# dsPIC_filter.net
KiCad netlist of a schematic drawn in Altium Designer
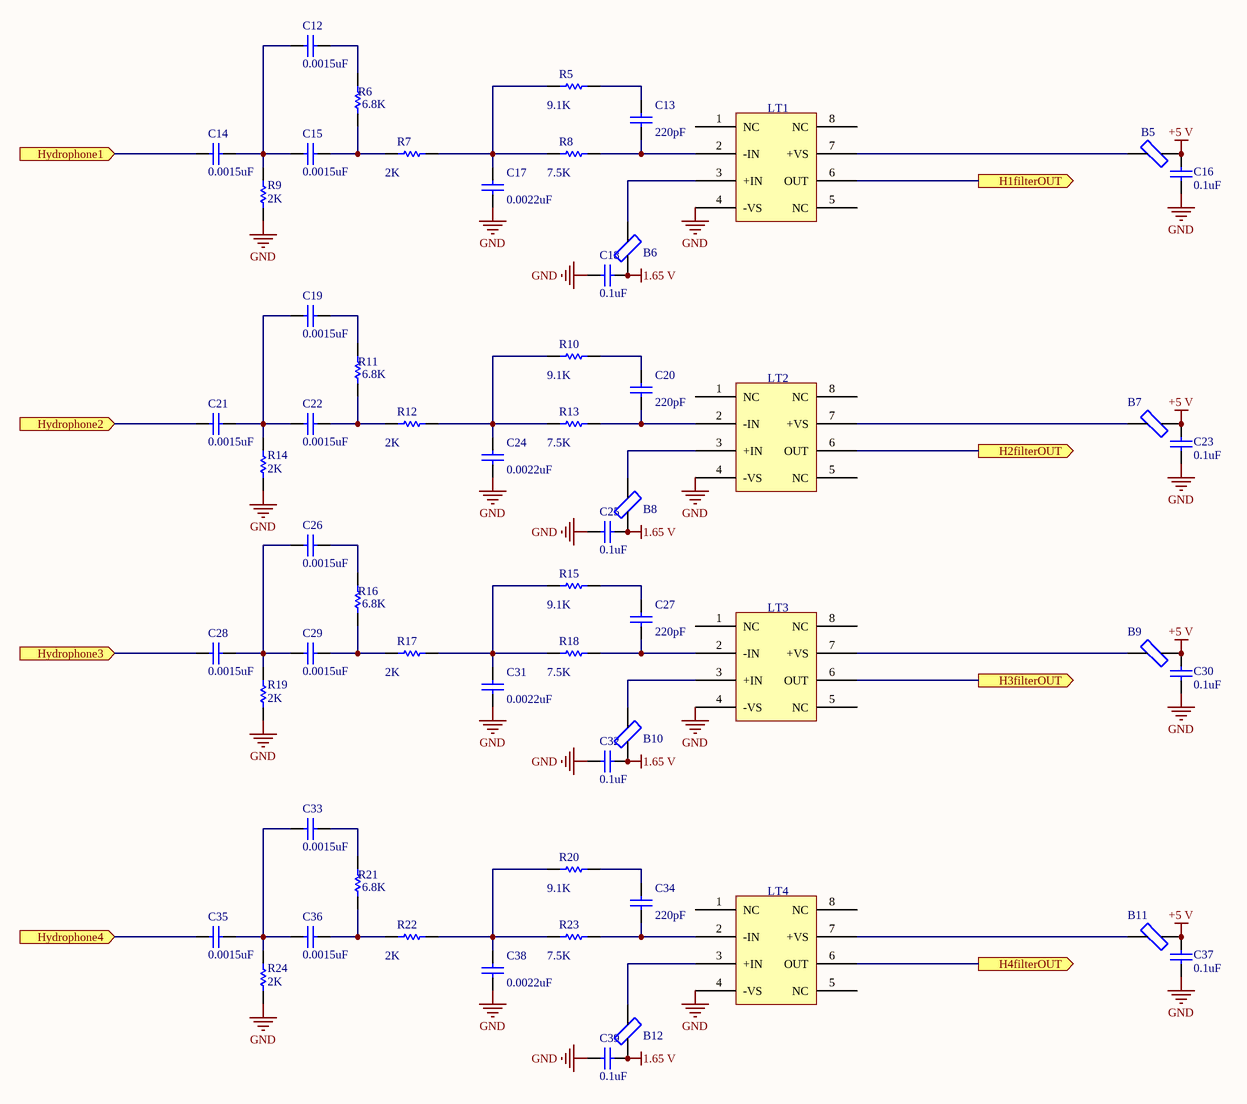
[diagram p0: dsPIC_filter.SchDoc]

(export (version "E")
  (design (tool "Eeschema 10.0.6"))
  (components
    (comp (ref "B5")
      (value "Ferrite Bead")
      (footprint "Capacitor 0603")
      (libsource (lib "PMUD") (part "Ferrite Bead"))
    )
    (comp (ref "B6")
      (value "Ferrite Bead")
      (footprint "Capacitor 0603")
      (libsource (lib "PMUD") (part "Ferrite Bead"))
    )
    (comp (ref "B7")
      (value "Ferrite Bead")
      (footprint "Capacitor 0603")
      (libsource (lib "PMUD") (part "Ferrite Bead"))
    )
    (comp (ref "B8")
      (value "Ferrite Bead")
      (footprint "Capacitor 0603")
      (libsource (lib "PMUD") (part "Ferrite Bead"))
    )
    (comp (ref "B9")
      (value "Ferrite Bead")
      (footprint "Capacitor 0603")
      (libsource (lib "PMUD") (part "Ferrite Bead"))
    )
    (comp (ref "B10")
      (value "Ferrite Bead")
      (footprint "Capacitor 0603")
      (libsource (lib "PMUD") (part "Ferrite Bead"))
    )
    (comp (ref "B11")
      (value "Ferrite Bead")
      (footprint "Capacitor 0603")
      (libsource (lib "PMUD") (part "Ferrite Bead"))
    )
    (comp (ref "B12")
      (value "Ferrite Bead")
      (footprint "Capacitor 0603")
      (libsource (lib "PMUD") (part "Ferrite Bead"))
    )
    (comp (ref "C12")
      (value "0.0015uF")
      (footprint "Capacitor 0603")
      (description "Capacitor")
      (fields (field (name "PUBLISHER") "Altium Limited"))
      (libsource (lib "My Parts Sch Components") (part "Cap"))
    )
    (comp (ref "C13")
      (value "220pF")
      (footprint "Capacitor 0603")
      (description "Capacitor")
      (fields (field (name "PUBLISHER") "Altium Limited"))
      (libsource (lib "My Parts Sch Components") (part "Cap"))
    )
    (comp (ref "C14")
      (value "0.0015uF")
      (footprint "Capacitor 0603")
      (description "Capacitor")
      (fields (field (name "PUBLISHER") "Altium Limited"))
      (libsource (lib "My Parts Sch Components") (part "Cap"))
    )
    (comp (ref "C15")
      (value "0.0015uF")
      (footprint "Capacitor 0603")
      (description "Capacitor")
      (fields (field (name "PUBLISHER") "Altium Limited"))
      (libsource (lib "My Parts Sch Components") (part "Cap"))
    )
    (comp (ref "C16")
      (value "0.1uF")
      (footprint "C1206")
      (description "Capacitor (Semiconductor SIM Model)")
      (fields (field (name "Comment") ".1uF 20V Ceramic Low ESR") (field (name "PUBLISHER") "Altium Limited"))
      (libsource (lib "Miscellaneous Devices") (part "Cap Semi"))
    )
    (comp (ref "C17")
      (value "0.0022uF")
      (footprint "Capacitor 0603")
      (description "Capacitor")
      (fields (field (name "PUBLISHER") "Altium Limited"))
      (libsource (lib "My Parts Sch Components") (part "Cap"))
    )
    (comp (ref "C18")
      (value "0.1uF")
      (footprint "C1206")
      (description "Capacitor (Semiconductor SIM Model)")
      (fields (field (name "Comment") ".1uF 20V Ceramic Low ESR") (field (name "PUBLISHER") "Altium Limited"))
      (libsource (lib "Miscellaneous Devices") (part "Cap Semi"))
    )
    (comp (ref "C19")
      (value "0.0015uF")
      (footprint "Capacitor 0603")
      (description "Capacitor")
      (fields (field (name "PUBLISHER") "Altium Limited"))
      (libsource (lib "My Parts Sch Components") (part "Cap"))
    )
    (comp (ref "C20")
      (value "220pF")
      (footprint "Capacitor 0603")
      (description "Capacitor")
      (fields (field (name "PUBLISHER") "Altium Limited"))
      (libsource (lib "My Parts Sch Components") (part "Cap"))
    )
    (comp (ref "C21")
      (value "0.0015uF")
      (footprint "Capacitor 0603")
      (description "Capacitor")
      (fields (field (name "PUBLISHER") "Altium Limited"))
      (libsource (lib "My Parts Sch Components") (part "Cap"))
    )
    (comp (ref "C22")
      (value "0.0015uF")
      (footprint "Capacitor 0603")
      (description "Capacitor")
      (fields (field (name "PUBLISHER") "Altium Limited"))
      (libsource (lib "My Parts Sch Components") (part "Cap"))
    )
    (comp (ref "C23")
      (value "0.1uF")
      (footprint "C1206")
      (description "Capacitor (Semiconductor SIM Model)")
      (fields (field (name "Comment") ".1uF 20V Ceramic Low ESR") (field (name "PUBLISHER") "Altium Limited"))
      (libsource (lib "Miscellaneous Devices") (part "Cap Semi"))
    )
    (comp (ref "C24")
      (value "0.0022uF")
      (footprint "Capacitor 0603")
      (description "Capacitor")
      (fields (field (name "PUBLISHER") "Altium Limited"))
      (libsource (lib "My Parts Sch Components") (part "Cap"))
    )
    (comp (ref "C25")
      (value "0.1uF")
      (footprint "C1206")
      (description "Capacitor (Semiconductor SIM Model)")
      (fields (field (name "Comment") ".1uF 20V Ceramic Low ESR") (field (name "PUBLISHER") "Altium Limited"))
      (libsource (lib "Miscellaneous Devices") (part "Cap Semi"))
    )
    (comp (ref "C26")
      (value "0.0015uF")
      (footprint "Capacitor 0603")
      (description "Capacitor")
      (fields (field (name "PUBLISHER") "Altium Limited"))
      (libsource (lib "My Parts Sch Components") (part "Cap"))
    )
    (comp (ref "C27")
      (value "220pF")
      (footprint "Capacitor 0603")
      (description "Capacitor")
      (fields (field (name "PUBLISHER") "Altium Limited"))
      (libsource (lib "My Parts Sch Components") (part "Cap"))
    )
    (comp (ref "C28")
      (value "0.0015uF")
      (footprint "Capacitor 0603")
      (description "Capacitor")
      (fields (field (name "PUBLISHER") "Altium Limited"))
      (libsource (lib "My Parts Sch Components") (part "Cap"))
    )
    (comp (ref "C29")
      (value "0.0015uF")
      (footprint "Capacitor 0603")
      (description "Capacitor")
      (fields (field (name "PUBLISHER") "Altium Limited"))
      (libsource (lib "My Parts Sch Components") (part "Cap"))
    )
    (comp (ref "C30")
      (value "0.1uF")
      (footprint "C1206")
      (description "Capacitor (Semiconductor SIM Model)")
      (fields (field (name "Comment") ".1uF 20V Ceramic Low ESR") (field (name "PUBLISHER") "Altium Limited"))
      (libsource (lib "Miscellaneous Devices") (part "Cap Semi"))
    )
    (comp (ref "C31")
      (value "0.0022uF")
      (footprint "Capacitor 0603")
      (description "Capacitor")
      (fields (field (name "PUBLISHER") "Altium Limited"))
      (libsource (lib "My Parts Sch Components") (part "Cap"))
    )
    (comp (ref "C32")
      (value "0.1uF")
      (footprint "C1206")
      (description "Capacitor (Semiconductor SIM Model)")
      (fields (field (name "Comment") ".1uF 20V Ceramic Low ESR") (field (name "PUBLISHER") "Altium Limited"))
      (libsource (lib "Miscellaneous Devices") (part "Cap Semi"))
    )
    (comp (ref "C33")
      (value "0.0015uF")
      (footprint "Capacitor 0603")
      (description "Capacitor")
      (fields (field (name "PUBLISHER") "Altium Limited"))
      (libsource (lib "My Parts Sch Components") (part "Cap"))
    )
    (comp (ref "C34")
      (value "220pF")
      (footprint "Capacitor 0603")
      (description "Capacitor")
      (fields (field (name "PUBLISHER") "Altium Limited"))
      (libsource (lib "My Parts Sch Components") (part "Cap"))
    )
    (comp (ref "C35")
      (value "0.0015uF")
      (footprint "Capacitor 0603")
      (description "Capacitor")
      (fields (field (name "PUBLISHER") "Altium Limited"))
      (libsource (lib "My Parts Sch Components") (part "Cap"))
    )
    (comp (ref "C36")
      (value "0.0015uF")
      (footprint "Capacitor 0603")
      (description "Capacitor")
      (fields (field (name "PUBLISHER") "Altium Limited"))
      (libsource (lib "My Parts Sch Components") (part "Cap"))
    )
    (comp (ref "C37")
      (value "0.1uF")
      (footprint "C1206")
      (description "Capacitor (Semiconductor SIM Model)")
      (fields (field (name "Comment") ".1uF 20V Ceramic Low ESR") (field (name "PUBLISHER") "Altium Limited"))
      (libsource (lib "Miscellaneous Devices") (part "Cap Semi"))
    )
    (comp (ref "C38")
      (value "0.0022uF")
      (footprint "Capacitor 0603")
      (description "Capacitor")
      (fields (field (name "PUBLISHER") "Altium Limited"))
      (libsource (lib "My Parts Sch Components") (part "Cap"))
    )
    (comp (ref "C39")
      (value "0.1uF")
      (footprint "C1206")
      (description "Capacitor (Semiconductor SIM Model)")
      (fields (field (name "Comment") ".1uF 20V Ceramic Low ESR") (field (name "PUBLISHER") "Altium Limited"))
      (libsource (lib "Miscellaneous Devices") (part "Cap Semi"))
    )
    (comp (ref "LT1")
      (value "LT1677 SO8 Package")
      (footprint "SO8")
      (libsource (lib "My Parts Sch Components") (part "LT1677"))
    )
    (comp (ref "LT2")
      (value "LT1677 SO8 Package")
      (footprint "SO8")
      (libsource (lib "My Parts Sch Components") (part "LT1677"))
    )
    (comp (ref "LT3")
      (value "LT1677 SO8 Package")
      (footprint "SO8")
      (libsource (lib "My Parts Sch Components") (part "LT1677"))
    )
    (comp (ref "LT4")
      (value "LT1677 SO8 Package")
      (footprint "SO8")
      (libsource (lib "My Parts Sch Components") (part "LT1677"))
    )
    (comp (ref "R5")
      (value "9.1K")
      (footprint "Capacitor 0603")
      (description "Resistor")
      (fields (field (name "PUBLISHER") "Altium Limited"))
      (libsource (lib "My Parts Sch Components") (part "Res1"))
    )
    (comp (ref "R6")
      (value "6.8K")
      (footprint "Capacitor 0603")
      (description "Resistor")
      (fields (field (name "PUBLISHER") "Altium Limited"))
      (libsource (lib "My Parts Sch Components") (part "Res1"))
    )
    (comp (ref "R7")
      (value "2K")
      (footprint "Capacitor 0603")
      (description "Resistor")
      (fields (field (name "PUBLISHER") "Altium Limited"))
      (libsource (lib "My Parts Sch Components") (part "Res1"))
    )
    (comp (ref "R8")
      (value "7.5K")
      (footprint "Capacitor 0603")
      (description "Resistor")
      (fields (field (name "PUBLISHER") "Altium Limited"))
      (libsource (lib "My Parts Sch Components") (part "Res1"))
    )
    (comp (ref "R9")
      (value "2K")
      (footprint "Capacitor 0603")
      (description "Resistor")
      (fields (field (name "PUBLISHER") "Altium Limited"))
      (libsource (lib "My Parts Sch Components") (part "Res1"))
    )
    (comp (ref "R10")
      (value "9.1K")
      (footprint "Capacitor 0603")
      (description "Resistor")
      (fields (field (name "PUBLISHER") "Altium Limited"))
      (libsource (lib "My Parts Sch Components") (part "Res1"))
    )
    (comp (ref "R11")
      (value "6.8K")
      (footprint "Capacitor 0603")
      (description "Resistor")
      (fields (field (name "PUBLISHER") "Altium Limited"))
      (libsource (lib "My Parts Sch Components") (part "Res1"))
    )
    (comp (ref "R12")
      (value "2K")
      (footprint "Capacitor 0603")
      (description "Resistor")
      (fields (field (name "PUBLISHER") "Altium Limited"))
      (libsource (lib "My Parts Sch Components") (part "Res1"))
    )
    (comp (ref "R13")
      (value "7.5K")
      (footprint "Capacitor 0603")
      (description "Resistor")
      (fields (field (name "PUBLISHER") "Altium Limited"))
      (libsource (lib "My Parts Sch Components") (part "Res1"))
    )
    (comp (ref "R14")
      (value "2K")
      (footprint "Capacitor 0603")
      (description "Resistor")
      (fields (field (name "PUBLISHER") "Altium Limited"))
      (libsource (lib "My Parts Sch Components") (part "Res1"))
    )
    (comp (ref "R15")
      (value "9.1K")
      (footprint "Capacitor 0603")
      (description "Resistor")
      (fields (field (name "PUBLISHER") "Altium Limited"))
      (libsource (lib "My Parts Sch Components") (part "Res1"))
    )
    (comp (ref "R16")
      (value "6.8K")
      (footprint "Capacitor 0603")
      (description "Resistor")
      (fields (field (name "PUBLISHER") "Altium Limited"))
      (libsource (lib "My Parts Sch Components") (part "Res1"))
    )
    (comp (ref "R17")
      (value "2K")
      (footprint "Capacitor 0603")
      (description "Resistor")
      (fields (field (name "PUBLISHER") "Altium Limited"))
      (libsource (lib "My Parts Sch Components") (part "Res1"))
    )
    (comp (ref "R18")
      (value "7.5K")
      (footprint "Capacitor 0603")
      (description "Resistor")
      (fields (field (name "PUBLISHER") "Altium Limited"))
      (libsource (lib "My Parts Sch Components") (part "Res1"))
    )
    (comp (ref "R19")
      (value "2K")
      (footprint "Capacitor 0603")
      (description "Resistor")
      (fields (field (name "PUBLISHER") "Altium Limited"))
      (libsource (lib "My Parts Sch Components") (part "Res1"))
    )
    (comp (ref "R20")
      (value "9.1K")
      (footprint "Capacitor 0603")
      (description "Resistor")
      (fields (field (name "PUBLISHER") "Altium Limited"))
      (libsource (lib "My Parts Sch Components") (part "Res1"))
    )
    (comp (ref "R21")
      (value "6.8K")
      (footprint "Capacitor 0603")
      (description "Resistor")
      (fields (field (name "PUBLISHER") "Altium Limited"))
      (libsource (lib "My Parts Sch Components") (part "Res1"))
    )
    (comp (ref "R22")
      (value "2K")
      (footprint "Capacitor 0603")
      (description "Resistor")
      (fields (field (name "PUBLISHER") "Altium Limited"))
      (libsource (lib "My Parts Sch Components") (part "Res1"))
    )
    (comp (ref "R23")
      (value "7.5K")
      (footprint "Capacitor 0603")
      (description "Resistor")
      (fields (field (name "PUBLISHER") "Altium Limited"))
      (libsource (lib "My Parts Sch Components") (part "Res1"))
    )
    (comp (ref "R24")
      (value "2K")
      (footprint "Capacitor 0603")
      (description "Resistor")
      (fields (field (name "PUBLISHER") "Altium Limited"))
      (libsource (lib "My Parts Sch Components") (part "Res1"))
    )
  )
  (nets
    (net (code "1") (name "+5 V") (class "Default")
      (node (ref "B11") (pin "1") (pinfunction "1_1") (pintype "passive"))
      (node (ref "B5") (pin "1") (pinfunction "1_1") (pintype "passive"))
      (node (ref "B7") (pin "1") (pinfunction "1_1") (pintype "passive"))
      (node (ref "B9") (pin "1") (pinfunction "1_1") (pintype "passive"))
      (node (ref "C16") (pin "1") (pinfunction "1_1") (pintype "passive"))
      (node (ref "C23") (pin "1") (pinfunction "1_1") (pintype "passive"))
      (node (ref "C30") (pin "1") (pinfunction "1_1") (pintype "passive"))
      (node (ref "C37") (pin "1") (pinfunction "1_1") (pintype "passive"))
    )
    (net (code "2") (name "/H1filterOUT") (class "Default")
      (node (ref "LT1") (pin "6") (pinfunction "OUT_6") (pintype "passive"))
    )
    (net (code "3") (name "/H2filterOUT") (class "Default")
      (node (ref "LT2") (pin "6") (pinfunction "OUT_6") (pintype "passive"))
    )
    (net (code "4") (name "/H3filterOUT") (class "Default")
      (node (ref "LT3") (pin "6") (pinfunction "OUT_6") (pintype "passive"))
    )
    (net (code "5") (name "/H4filterOUT") (class "Default")
      (node (ref "LT4") (pin "6") (pinfunction "OUT_6") (pintype "passive"))
    )
    (net (code "6") (name "/Hydrophone1") (class "Default")
      (node (ref "C14") (pin "2") (pinfunction "2_2") (pintype "passive"))
    )
    (net (code "7") (name "/Hydrophone2") (class "Default")
      (node (ref "C21") (pin "2") (pinfunction "2_2") (pintype "passive"))
    )
    (net (code "8") (name "/Hydrophone3") (class "Default")
      (node (ref "C28") (pin "2") (pinfunction "2_2") (pintype "passive"))
    )
    (net (code "9") (name "/Hydrophone4") (class "Default")
      (node (ref "C35") (pin "2") (pinfunction "2_2") (pintype "passive"))
    )
    (net (code "10") (name "1.65 V") (class "Default")
      (node (ref "B10") (pin "1") (pinfunction "1_1") (pintype "passive"))
      (node (ref "B12") (pin "1") (pinfunction "1_1") (pintype "passive"))
      (node (ref "B6") (pin "1") (pinfunction "1_1") (pintype "passive"))
      (node (ref "B8") (pin "1") (pinfunction "1_1") (pintype "passive"))
      (node (ref "C18") (pin "1") (pinfunction "1_1") (pintype "passive"))
      (node (ref "C25") (pin "1") (pinfunction "1_1") (pintype "passive"))
      (node (ref "C32") (pin "1") (pinfunction "1_1") (pintype "passive"))
      (node (ref "C39") (pin "1") (pinfunction "1_1") (pintype "passive"))
    )
    (net (code "11") (name "GND") (class "Default")
      (node (ref "C16") (pin "2") (pinfunction "2_2") (pintype "passive"))
      (node (ref "C17") (pin "1") (pinfunction "1_1") (pintype "passive"))
      (node (ref "C18") (pin "2") (pinfunction "2_2") (pintype "passive"))
      (node (ref "C23") (pin "2") (pinfunction "2_2") (pintype "passive"))
      (node (ref "C24") (pin "1") (pinfunction "1_1") (pintype "passive"))
      (node (ref "C25") (pin "2") (pinfunction "2_2") (pintype "passive"))
      (node (ref "C30") (pin "2") (pinfunction "2_2") (pintype "passive"))
      (node (ref "C31") (pin "1") (pinfunction "1_1") (pintype "passive"))
      (node (ref "C32") (pin "2") (pinfunction "2_2") (pintype "passive"))
      (node (ref "C37") (pin "2") (pinfunction "2_2") (pintype "passive"))
      (node (ref "C38") (pin "1") (pinfunction "1_1") (pintype "passive"))
      (node (ref "C39") (pin "2") (pinfunction "2_2") (pintype "passive"))
      (node (ref "LT1") (pin "4") (pinfunction "-VS_4") (pintype "passive"))
      (node (ref "LT2") (pin "4") (pinfunction "-VS_4") (pintype "passive"))
      (node (ref "LT3") (pin "4") (pinfunction "-VS_4") (pintype "passive"))
      (node (ref "LT4") (pin "4") (pinfunction "-VS_4") (pintype "passive"))
      (node (ref "R14") (pin "1") (pinfunction "1_1") (pintype "passive"))
      (node (ref "R19") (pin "1") (pinfunction "1_1") (pintype "passive"))
      (node (ref "R24") (pin "1") (pinfunction "1_1") (pintype "passive"))
      (node (ref "R9") (pin "1") (pinfunction "1_1") (pintype "passive"))
    )
    (net (code "12") (name "Net-(C12-Pad1)") (class "Default")
      (node (ref "C12") (pin "1") (pinfunction "1_1") (pintype "passive"))
      (node (ref "R6") (pin "2") (pinfunction "2_2") (pintype "passive"))
    )
    (net (code "13") (name "Net-(C12-Pad2)") (class "Default")
      (node (ref "C12") (pin "2") (pinfunction "2_2") (pintype "passive"))
      (node (ref "C14") (pin "1") (pinfunction "1_1") (pintype "passive"))
      (node (ref "C15") (pin "2") (pinfunction "2_2") (pintype "passive"))
      (node (ref "R9") (pin "2") (pinfunction "2_2") (pintype "passive"))
    )
    (net (code "14") (name "Net-(C13-Pad2)") (class "Default")
      (node (ref "C13") (pin "2") (pinfunction "2_2") (pintype "passive"))
      (node (ref "R5") (pin "2") (pinfunction "2_2") (pintype "passive"))
    )
    (net (code "15") (name "Net-(C15-Pad1)") (class "Default")
      (node (ref "C15") (pin "1") (pinfunction "1_1") (pintype "passive"))
      (node (ref "R6") (pin "1") (pinfunction "1_1") (pintype "passive"))
      (node (ref "R7") (pin "1") (pinfunction "1_1") (pintype "passive"))
    )
    (net (code "16") (name "Net-(C17-Pad2)") (class "Default")
      (node (ref "C17") (pin "2") (pinfunction "2_2") (pintype "passive"))
      (node (ref "R5") (pin "1") (pinfunction "1_1") (pintype "passive"))
      (node (ref "R7") (pin "2") (pinfunction "2_2") (pintype "passive"))
      (node (ref "R8") (pin "1") (pinfunction "1_1") (pintype "passive"))
    )
    (net (code "17") (name "Net-(C19-Pad1)") (class "Default")
      (node (ref "C19") (pin "1") (pinfunction "1_1") (pintype "passive"))
      (node (ref "R11") (pin "2") (pinfunction "2_2") (pintype "passive"))
    )
    (net (code "18") (name "Net-(C19-Pad2)") (class "Default")
      (node (ref "C19") (pin "2") (pinfunction "2_2") (pintype "passive"))
      (node (ref "C21") (pin "1") (pinfunction "1_1") (pintype "passive"))
      (node (ref "C22") (pin "2") (pinfunction "2_2") (pintype "passive"))
      (node (ref "R14") (pin "2") (pinfunction "2_2") (pintype "passive"))
    )
    (net (code "19") (name "Net-(C20-Pad2)") (class "Default")
      (node (ref "C20") (pin "2") (pinfunction "2_2") (pintype "passive"))
      (node (ref "R10") (pin "2") (pinfunction "2_2") (pintype "passive"))
    )
    (net (code "20") (name "Net-(C22-Pad1)") (class "Default")
      (node (ref "C22") (pin "1") (pinfunction "1_1") (pintype "passive"))
      (node (ref "R11") (pin "1") (pinfunction "1_1") (pintype "passive"))
      (node (ref "R12") (pin "1") (pinfunction "1_1") (pintype "passive"))
    )
    (net (code "21") (name "Net-(C24-Pad2)") (class "Default")
      (node (ref "C24") (pin "2") (pinfunction "2_2") (pintype "passive"))
      (node (ref "R10") (pin "1") (pinfunction "1_1") (pintype "passive"))
      (node (ref "R12") (pin "2") (pinfunction "2_2") (pintype "passive"))
      (node (ref "R13") (pin "1") (pinfunction "1_1") (pintype "passive"))
    )
    (net (code "22") (name "Net-(C26-Pad1)") (class "Default")
      (node (ref "C26") (pin "1") (pinfunction "1_1") (pintype "passive"))
      (node (ref "R16") (pin "2") (pinfunction "2_2") (pintype "passive"))
    )
    (net (code "23") (name "Net-(C26-Pad2)") (class "Default")
      (node (ref "C26") (pin "2") (pinfunction "2_2") (pintype "passive"))
      (node (ref "C28") (pin "1") (pinfunction "1_1") (pintype "passive"))
      (node (ref "C29") (pin "2") (pinfunction "2_2") (pintype "passive"))
      (node (ref "R19") (pin "2") (pinfunction "2_2") (pintype "passive"))
    )
    (net (code "24") (name "Net-(C27-Pad2)") (class "Default")
      (node (ref "C27") (pin "2") (pinfunction "2_2") (pintype "passive"))
      (node (ref "R15") (pin "2") (pinfunction "2_2") (pintype "passive"))
    )
    (net (code "25") (name "Net-(C29-Pad1)") (class "Default")
      (node (ref "C29") (pin "1") (pinfunction "1_1") (pintype "passive"))
      (node (ref "R16") (pin "1") (pinfunction "1_1") (pintype "passive"))
      (node (ref "R17") (pin "1") (pinfunction "1_1") (pintype "passive"))
    )
    (net (code "26") (name "Net-(C31-Pad2)") (class "Default")
      (node (ref "C31") (pin "2") (pinfunction "2_2") (pintype "passive"))
      (node (ref "R15") (pin "1") (pinfunction "1_1") (pintype "passive"))
      (node (ref "R17") (pin "2") (pinfunction "2_2") (pintype "passive"))
      (node (ref "R18") (pin "1") (pinfunction "1_1") (pintype "passive"))
    )
    (net (code "27") (name "Net-(C33-Pad1)") (class "Default")
      (node (ref "C33") (pin "1") (pinfunction "1_1") (pintype "passive"))
      (node (ref "R21") (pin "2") (pinfunction "2_2") (pintype "passive"))
    )
    (net (code "28") (name "Net-(C33-Pad2)") (class "Default")
      (node (ref "C33") (pin "2") (pinfunction "2_2") (pintype "passive"))
      (node (ref "C35") (pin "1") (pinfunction "1_1") (pintype "passive"))
      (node (ref "C36") (pin "2") (pinfunction "2_2") (pintype "passive"))
      (node (ref "R24") (pin "2") (pinfunction "2_2") (pintype "passive"))
    )
    (net (code "29") (name "Net-(C34-Pad2)") (class "Default")
      (node (ref "C34") (pin "2") (pinfunction "2_2") (pintype "passive"))
      (node (ref "R20") (pin "2") (pinfunction "2_2") (pintype "passive"))
    )
    (net (code "30") (name "Net-(C36-Pad1)") (class "Default")
      (node (ref "C36") (pin "1") (pinfunction "1_1") (pintype "passive"))
      (node (ref "R21") (pin "1") (pinfunction "1_1") (pintype "passive"))
      (node (ref "R22") (pin "1") (pinfunction "1_1") (pintype "passive"))
    )
    (net (code "31") (name "Net-(C38-Pad2)") (class "Default")
      (node (ref "C38") (pin "2") (pinfunction "2_2") (pintype "passive"))
      (node (ref "R20") (pin "1") (pinfunction "1_1") (pintype "passive"))
      (node (ref "R22") (pin "2") (pinfunction "2_2") (pintype "passive"))
      (node (ref "R23") (pin "1") (pinfunction "1_1") (pintype "passive"))
    )
    (net (code "32") (name "Net-(LT1-+IN)") (class "Default")
      (node (ref "B6") (pin "2") (pinfunction "2_2") (pintype "passive"))
      (node (ref "LT1") (pin "3") (pinfunction "+IN_3") (pintype "passive"))
    )
    (net (code "33") (name "Net-(LT1-+VS)") (class "Default")
      (node (ref "B5") (pin "2") (pinfunction "2_2") (pintype "passive"))
      (node (ref "LT1") (pin "7") (pinfunction "+VS_7") (pintype "passive"))
    )
    (net (code "34") (name "Net-(LT1--IN)") (class "Default")
      (node (ref "C13") (pin "1") (pinfunction "1_1") (pintype "passive"))
      (node (ref "LT1") (pin "2") (pinfunction "-IN_2") (pintype "passive"))
      (node (ref "R8") (pin "2") (pinfunction "2_2") (pintype "passive"))
    )
    (net (code "35") (name "Net-(LT2-+IN)") (class "Default")
      (node (ref "B8") (pin "2") (pinfunction "2_2") (pintype "passive"))
      (node (ref "LT2") (pin "3") (pinfunction "+IN_3") (pintype "passive"))
    )
    (net (code "36") (name "Net-(LT2-+VS)") (class "Default")
      (node (ref "B7") (pin "2") (pinfunction "2_2") (pintype "passive"))
      (node (ref "LT2") (pin "7") (pinfunction "+VS_7") (pintype "passive"))
    )
    (net (code "37") (name "Net-(LT2--IN)") (class "Default")
      (node (ref "C20") (pin "1") (pinfunction "1_1") (pintype "passive"))
      (node (ref "LT2") (pin "2") (pinfunction "-IN_2") (pintype "passive"))
      (node (ref "R13") (pin "2") (pinfunction "2_2") (pintype "passive"))
    )
    (net (code "38") (name "Net-(LT3-+IN)") (class "Default")
      (node (ref "B10") (pin "2") (pinfunction "2_2") (pintype "passive"))
      (node (ref "LT3") (pin "3") (pinfunction "+IN_3") (pintype "passive"))
    )
    (net (code "39") (name "Net-(LT3-+VS)") (class "Default")
      (node (ref "B9") (pin "2") (pinfunction "2_2") (pintype "passive"))
      (node (ref "LT3") (pin "7") (pinfunction "+VS_7") (pintype "passive"))
    )
    (net (code "40") (name "Net-(LT3--IN)") (class "Default")
      (node (ref "C27") (pin "1") (pinfunction "1_1") (pintype "passive"))
      (node (ref "LT3") (pin "2") (pinfunction "-IN_2") (pintype "passive"))
      (node (ref "R18") (pin "2") (pinfunction "2_2") (pintype "passive"))
    )
    (net (code "41") (name "Net-(LT4-+IN)") (class "Default")
      (node (ref "B12") (pin "2") (pinfunction "2_2") (pintype "passive"))
      (node (ref "LT4") (pin "3") (pinfunction "+IN_3") (pintype "passive"))
    )
    (net (code "42") (name "Net-(LT4-+VS)") (class "Default")
      (node (ref "B11") (pin "2") (pinfunction "2_2") (pintype "passive"))
      (node (ref "LT4") (pin "7") (pinfunction "+VS_7") (pintype "passive"))
    )
    (net (code "43") (name "Net-(LT4--IN)") (class "Default")
      (node (ref "C34") (pin "1") (pinfunction "1_1") (pintype "passive"))
      (node (ref "LT4") (pin "2") (pinfunction "-IN_2") (pintype "passive"))
      (node (ref "R23") (pin "2") (pinfunction "2_2") (pintype "passive"))
    )
    (net (code "44") (name "unconnected-(LT1-NC-Pad1)") (class "Default")
      (node (ref "LT1") (pin "1") (pinfunction "NC_1") (pintype "passive"))
    )
    (net (code "45") (name "unconnected-(LT1-NC-Pad5)") (class "Default")
      (node (ref "LT1") (pin "5") (pinfunction "NC_5") (pintype "passive"))
    )
    (net (code "46") (name "unconnected-(LT1-NC-Pad8)") (class "Default")
      (node (ref "LT1") (pin "8") (pinfunction "NC_8") (pintype "passive"))
    )
    (net (code "47") (name "unconnected-(LT2-NC-Pad1)") (class "Default")
      (node (ref "LT2") (pin "1") (pinfunction "NC_1") (pintype "passive"))
    )
    (net (code "48") (name "unconnected-(LT2-NC-Pad5)") (class "Default")
      (node (ref "LT2") (pin "5") (pinfunction "NC_5") (pintype "passive"))
    )
    (net (code "49") (name "unconnected-(LT2-NC-Pad8)") (class "Default")
      (node (ref "LT2") (pin "8") (pinfunction "NC_8") (pintype "passive"))
    )
    (net (code "50") (name "unconnected-(LT3-NC-Pad1)") (class "Default")
      (node (ref "LT3") (pin "1") (pinfunction "NC_1") (pintype "passive"))
    )
    (net (code "51") (name "unconnected-(LT3-NC-Pad5)") (class "Default")
      (node (ref "LT3") (pin "5") (pinfunction "NC_5") (pintype "passive"))
    )
    (net (code "52") (name "unconnected-(LT3-NC-Pad8)") (class "Default")
      (node (ref "LT3") (pin "8") (pinfunction "NC_8") (pintype "passive"))
    )
    (net (code "53") (name "unconnected-(LT4-NC-Pad1)") (class "Default")
      (node (ref "LT4") (pin "1") (pinfunction "NC_1") (pintype "passive"))
    )
    (net (code "54") (name "unconnected-(LT4-NC-Pad5)") (class "Default")
      (node (ref "LT4") (pin "5") (pinfunction "NC_5") (pintype "passive"))
    )
    (net (code "55") (name "unconnected-(LT4-NC-Pad8)") (class "Default")
      (node (ref "LT4") (pin "8") (pinfunction "NC_8") (pintype "passive"))
    )
  )
)
